# SOLENOID-SSR.net
KiCad netlist of a schematic drawn in Altium Designer
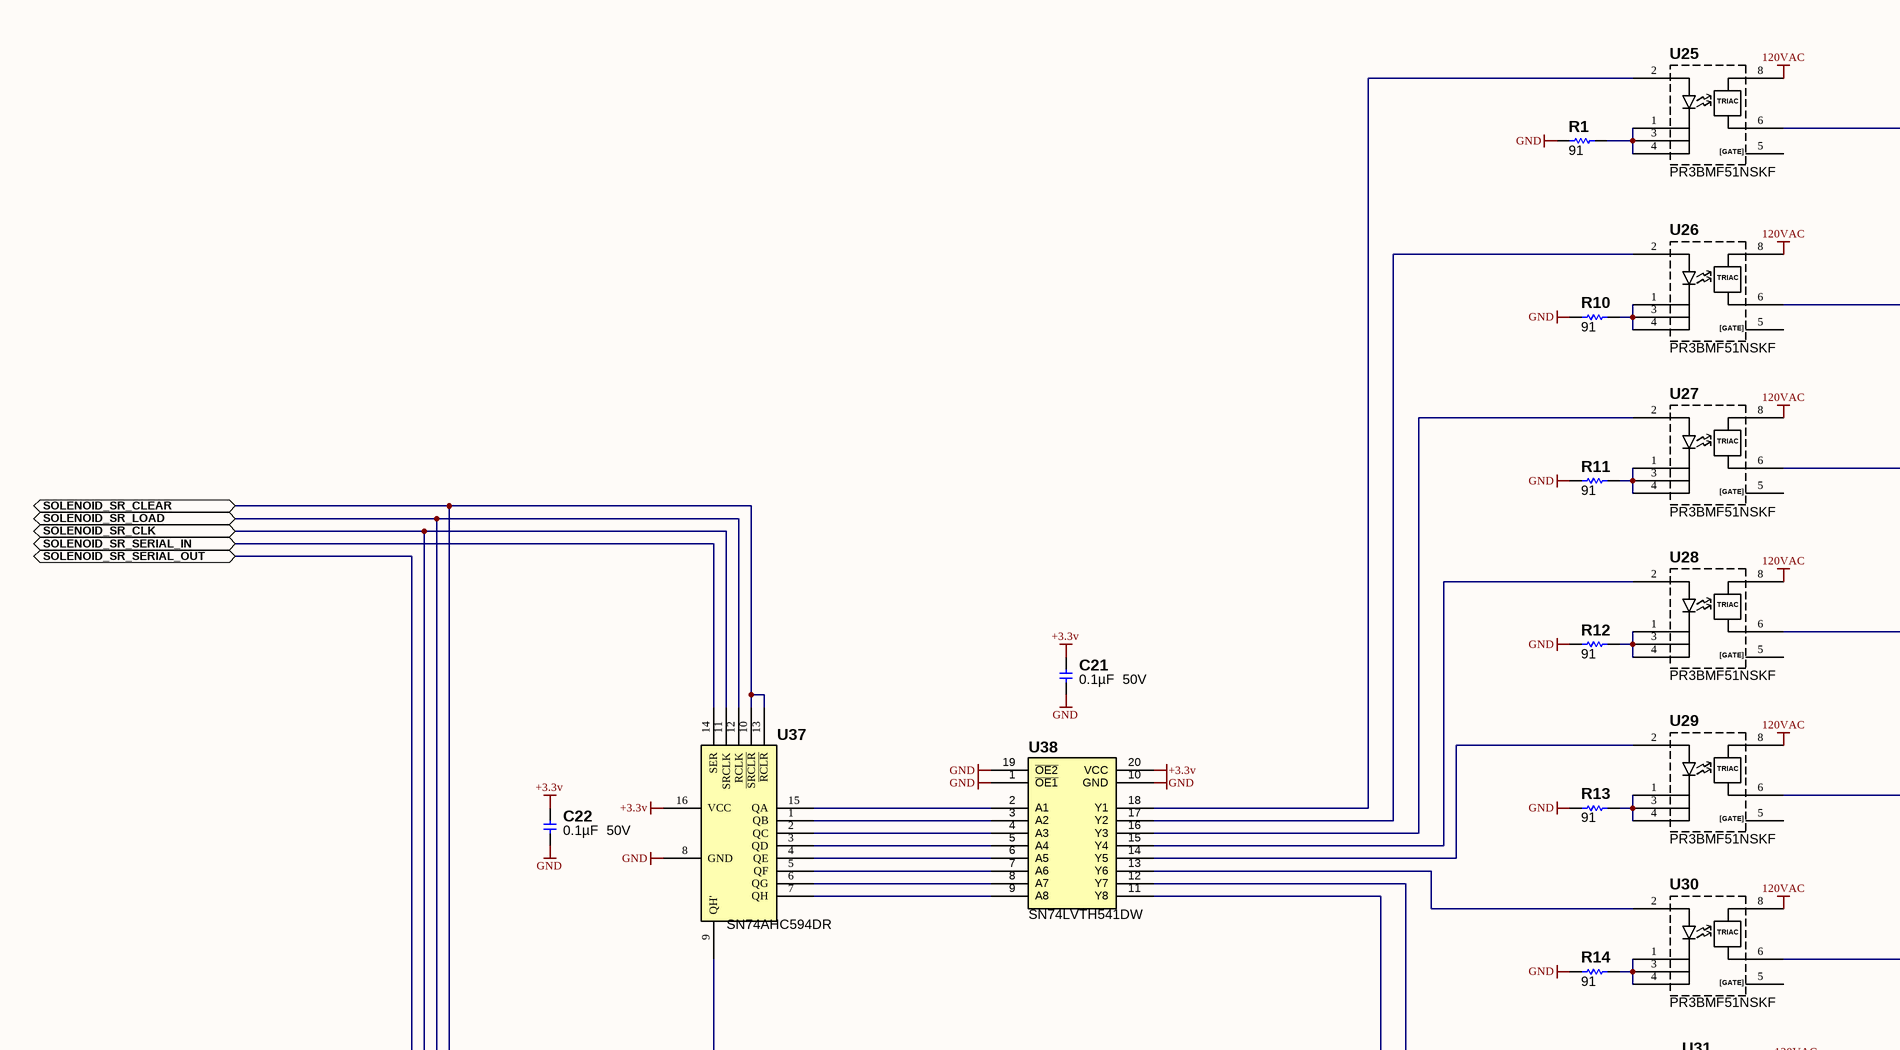
[diagram p0: SOLENOID-SSR.SchDoc, top left]
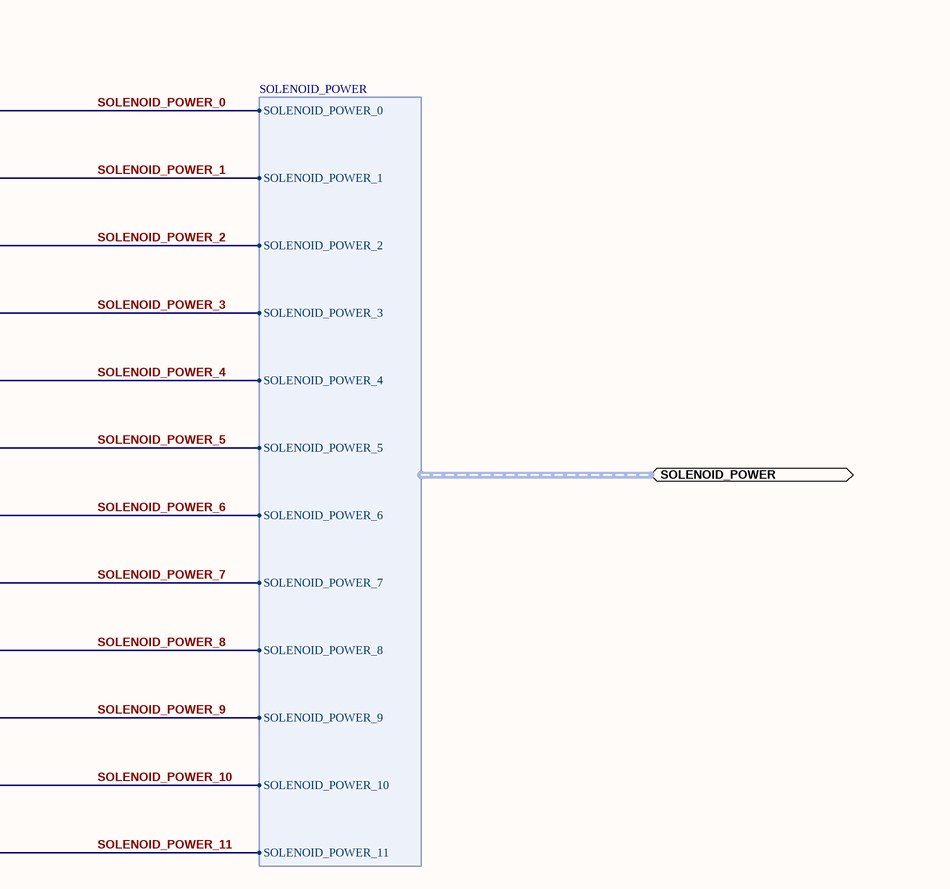
[diagram p1: SOLENOID-SSR.SchDoc, top right]
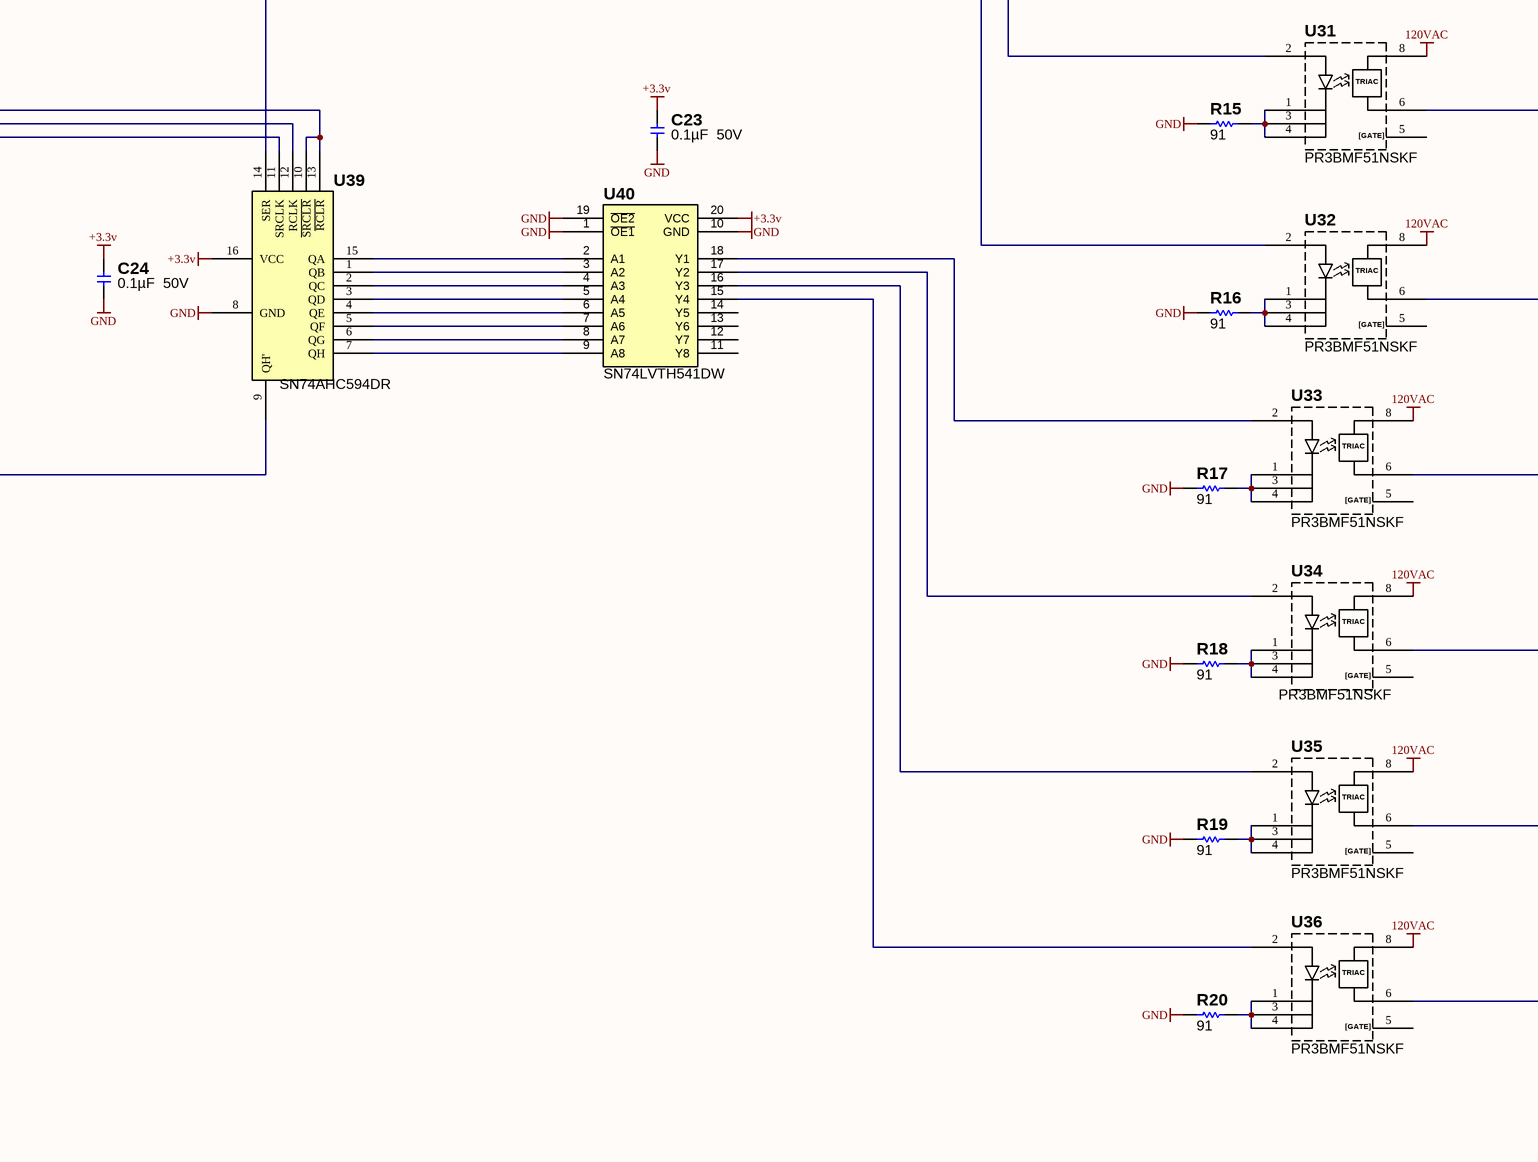
[diagram p2: SOLENOID-SSR.SchDoc, bottom left]
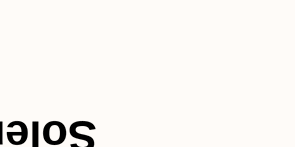
[diagram p3: SOLENOID-SSR.SchDoc, bottom right]

(export (version "E")
  (design (tool "Eeschema 10.0.6"))
  (components
    (comp (ref "C21")
      (value "0.1µF  50V")
      (footprint "C0805_LD")
      (description "CAP CER 0.1UF 50V 10% X7R 0805")
      (fields
        (field (name "MANUFACTURER PART NUMBER") "GRM21BR71H104KA01L")
        (field (name "MANUFACTURER") "Murata Electronics North America")
      )
      (libsource (lib "Capacitors") (part "C_2P_NP"))
    )
    (comp (ref "C22")
      (value "0.1µF  50V")
      (footprint "C0805_LD")
      (description "CAP CER 0.1UF 50V 10% X7R 0805")
      (fields
        (field (name "MANUFACTURER PART NUMBER") "GRM21BR71H104KA01L")
        (field (name "MANUFACTURER") "Murata Electronics North America")
      )
      (libsource (lib "Capacitors") (part "C_2P_NP"))
    )
    (comp (ref "C23")
      (value "0.1µF  50V")
      (footprint "C0805_LD")
      (description "CAP CER 0.1UF 50V 10% X7R 0805")
      (fields
        (field (name "MANUFACTURER PART NUMBER") "GRM21BR71H104KA01L")
        (field (name "MANUFACTURER") "Murata Electronics North America")
      )
      (libsource (lib "Capacitors") (part "C_2P_NP"))
    )
    (comp (ref "C24")
      (value "0.1µF  50V")
      (footprint "C0805_LD")
      (description "CAP CER 0.1UF 50V 10% X7R 0805")
      (fields
        (field (name "MANUFACTURER PART NUMBER") "GRM21BR71H104KA01L")
        (field (name "MANUFACTURER") "Murata Electronics North America")
      )
      (libsource (lib "Capacitors") (part "C_2P_NP"))
    )
    (comp (ref "R1")
      (value "91")
      (footprint "R0805_LD")
      (description "RES 91 OHM 1/8W 1% 0805 SMD")
      (fields
        (field (name "MANUFACTURER PART NUMBER") "ERJ-6ENF91R0V")
        (field (name "MANUFACTURER") "Panasonic Electronic Components")
      )
      (libsource (lib "Resistors") (part "R_2P"))
    )
    (comp (ref "R10")
      (value "91")
      (footprint "R0805_LD")
      (description "RES 91 OHM 1/8W 1% 0805 SMD")
      (fields
        (field (name "MANUFACTURER PART NUMBER") "ERJ-6ENF91R0V")
        (field (name "MANUFACTURER") "Panasonic Electronic Components")
      )
      (libsource (lib "Resistors") (part "R_2P"))
    )
    (comp (ref "R11")
      (value "91")
      (footprint "R0805_LD")
      (description "RES 91 OHM 1/8W 1% 0805 SMD")
      (fields
        (field (name "MANUFACTURER PART NUMBER") "ERJ-6ENF91R0V")
        (field (name "MANUFACTURER") "Panasonic Electronic Components")
      )
      (libsource (lib "Resistors") (part "R_2P"))
    )
    (comp (ref "R12")
      (value "91")
      (footprint "R0805_LD")
      (description "RES 91 OHM 1/8W 1% 0805 SMD")
      (fields
        (field (name "MANUFACTURER PART NUMBER") "ERJ-6ENF91R0V")
        (field (name "MANUFACTURER") "Panasonic Electronic Components")
      )
      (libsource (lib "Resistors") (part "R_2P"))
    )
    (comp (ref "R13")
      (value "91")
      (footprint "R0805_LD")
      (description "RES 91 OHM 1/8W 1% 0805 SMD")
      (fields
        (field (name "MANUFACTURER PART NUMBER") "ERJ-6ENF91R0V")
        (field (name "MANUFACTURER") "Panasonic Electronic Components")
      )
      (libsource (lib "Resistors") (part "R_2P"))
    )
    (comp (ref "R14")
      (value "91")
      (footprint "R0805_LD")
      (description "RES 91 OHM 1/8W 1% 0805 SMD")
      (fields
        (field (name "MANUFACTURER PART NUMBER") "ERJ-6ENF91R0V")
        (field (name "MANUFACTURER") "Panasonic Electronic Components")
      )
      (libsource (lib "Resistors") (part "R_2P"))
    )
    (comp (ref "R15")
      (value "91")
      (footprint "R0805_LD")
      (description "RES 91 OHM 1/8W 1% 0805 SMD")
      (fields
        (field (name "MANUFACTURER PART NUMBER") "ERJ-6ENF91R0V")
        (field (name "MANUFACTURER") "Panasonic Electronic Components")
      )
      (libsource (lib "Resistors") (part "R_2P"))
    )
    (comp (ref "R16")
      (value "91")
      (footprint "R0805_LD")
      (description "RES 91 OHM 1/8W 1% 0805 SMD")
      (fields
        (field (name "MANUFACTURER PART NUMBER") "ERJ-6ENF91R0V")
        (field (name "MANUFACTURER") "Panasonic Electronic Components")
      )
      (libsource (lib "Resistors") (part "R_2P"))
    )
    (comp (ref "R17")
      (value "91")
      (footprint "R0805_LD")
      (description "RES 91 OHM 1/8W 1% 0805 SMD")
      (fields
        (field (name "MANUFACTURER PART NUMBER") "ERJ-6ENF91R0V")
        (field (name "MANUFACTURER") "Panasonic Electronic Components")
      )
      (libsource (lib "Resistors") (part "R_2P"))
    )
    (comp (ref "R18")
      (value "91")
      (footprint "R0805_LD")
      (description "RES 91 OHM 1/8W 1% 0805 SMD")
      (fields
        (field (name "MANUFACTURER PART NUMBER") "ERJ-6ENF91R0V")
        (field (name "MANUFACTURER") "Panasonic Electronic Components")
      )
      (libsource (lib "Resistors") (part "R_2P"))
    )
    (comp (ref "R19")
      (value "91")
      (footprint "R0805_LD")
      (description "RES 91 OHM 1/8W 1% 0805 SMD")
      (fields
        (field (name "MANUFACTURER PART NUMBER") "ERJ-6ENF91R0V")
        (field (name "MANUFACTURER") "Panasonic Electronic Components")
      )
      (libsource (lib "Resistors") (part "R_2P"))
    )
    (comp (ref "R20")
      (value "91")
      (footprint "R0805_LD")
      (description "RES 91 OHM 1/8W 1% 0805 SMD")
      (fields
        (field (name "MANUFACTURER PART NUMBER") "ERJ-6ENF91R0V")
        (field (name "MANUFACTURER") "Panasonic Electronic Components")
      )
      (libsource (lib "Resistors") (part "R_2P"))
    )
    (comp (ref "U25")
      (value "PR3BMF51NSKF")
      (footprint "DIP8_NO_PIN7")
      (description "RELAY SSR 10MA 240V 1.2A 8-DIP")
      (fields (field (name "MANUFACTURER") "Sharp Microelectronics"))
      (libsource (lib "eIC") (part "PR3BMF51NSKF"))
    )
    (comp (ref "U26")
      (value "PR3BMF51NSKF")
      (footprint "DIP8_NO_PIN7")
      (description "RELAY SSR 10MA 240V 1.2A 8-DIP")
      (fields (field (name "MANUFACTURER") "Sharp Microelectronics"))
      (libsource (lib "eIC") (part "PR3BMF51NSKF"))
    )
    (comp (ref "U27")
      (value "PR3BMF51NSKF")
      (footprint "DIP8_NO_PIN7")
      (description "RELAY SSR 10MA 240V 1.2A 8-DIP")
      (fields (field (name "MANUFACTURER") "Sharp Microelectronics"))
      (libsource (lib "eIC") (part "PR3BMF51NSKF"))
    )
    (comp (ref "U28")
      (value "PR3BMF51NSKF")
      (footprint "DIP8_NO_PIN7")
      (description "RELAY SSR 10MA 240V 1.2A 8-DIP")
      (fields (field (name "MANUFACTURER") "Sharp Microelectronics"))
      (libsource (lib "eIC") (part "PR3BMF51NSKF"))
    )
    (comp (ref "U29")
      (value "PR3BMF51NSKF")
      (footprint "DIP8_NO_PIN7")
      (description "RELAY SSR 10MA 240V 1.2A 8-DIP")
      (fields (field (name "MANUFACTURER") "Sharp Microelectronics"))
      (libsource (lib "eIC") (part "PR3BMF51NSKF"))
    )
    (comp (ref "U30")
      (value "PR3BMF51NSKF")
      (footprint "DIP8_NO_PIN7")
      (description "RELAY SSR 10MA 240V 1.2A 8-DIP")
      (fields (field (name "MANUFACTURER") "Sharp Microelectronics"))
      (libsource (lib "eIC") (part "PR3BMF51NSKF"))
    )
    (comp (ref "U31")
      (value "PR3BMF51NSKF")
      (footprint "DIP8_NO_PIN7")
      (description "RELAY SSR 10MA 240V 1.2A 8-DIP")
      (fields (field (name "MANUFACTURER") "Sharp Microelectronics"))
      (libsource (lib "eIC") (part "PR3BMF51NSKF"))
    )
    (comp (ref "U32")
      (value "PR3BMF51NSKF")
      (footprint "DIP8_NO_PIN7")
      (description "RELAY SSR 10MA 240V 1.2A 8-DIP")
      (fields (field (name "MANUFACTURER") "Sharp Microelectronics"))
      (libsource (lib "eIC") (part "PR3BMF51NSKF"))
    )
    (comp (ref "U33")
      (value "PR3BMF51NSKF")
      (footprint "DIP8_NO_PIN7")
      (description "RELAY SSR 10MA 240V 1.2A 8-DIP")
      (fields (field (name "MANUFACTURER") "Sharp Microelectronics"))
      (libsource (lib "eIC") (part "PR3BMF51NSKF"))
    )
    (comp (ref "U34")
      (value "PR3BMF51NSKF")
      (footprint "DIP8_NO_PIN7")
      (description "RELAY SSR 10MA 240V 1.2A 8-DIP")
      (fields (field (name "MANUFACTURER") "Sharp Microelectronics"))
      (libsource (lib "eIC") (part "PR3BMF51NSKF"))
    )
    (comp (ref "U35")
      (value "PR3BMF51NSKF")
      (footprint "DIP8_NO_PIN7")
      (description "RELAY SSR 10MA 240V 1.2A 8-DIP")
      (fields (field (name "MANUFACTURER") "Sharp Microelectronics"))
      (libsource (lib "eIC") (part "PR3BMF51NSKF"))
    )
    (comp (ref "U36")
      (value "PR3BMF51NSKF")
      (footprint "DIP8_NO_PIN7")
      (description "RELAY SSR 10MA 240V 1.2A 8-DIP")
      (fields (field (name "MANUFACTURER") "Sharp Microelectronics"))
      (libsource (lib "eIC") (part "PR3BMF51NSKF"))
    )
    (comp (ref "U37")
      (value "SN74AHC594DR")
      (footprint "SOIC127P600X145-16L")
      (description "IC SHIFT REGISTER 8BIT 16-SOIC")
      (fields (field (name "MANUFACTURER") "Texas Instruments"))
      (libsource (lib "eIC") (part "SN74AHC594DR"))
    )
    (comp (ref "U38")
      (value "SN74LVTH541DW")
      (footprint "SOIC127P1030X265-20L")
      (description "IC BUFF/DVR TRI-ST 8BIT 20SOIC")
      (fields (field (name "MANUFACTURER") "Texas Instruments"))
      (libsource (lib "eIC") (part "SN74LVTH541DW"))
    )
    (comp (ref "U39")
      (value "SN74AHC594DR")
      (footprint "SOIC127P600X145-16L")
      (description "IC SHIFT REGISTER 8BIT 16-SOIC")
      (fields (field (name "MANUFACTURER") "Texas Instruments"))
      (libsource (lib "eIC") (part "SN74AHC594DR"))
    )
    (comp (ref "U40")
      (value "SN74LVTH541DW")
      (footprint "SOIC127P1030X265-20L")
      (description "IC BUFF/DVR TRI-ST 8BIT 20SOIC")
      (fields (field (name "MANUFACTURER") "Texas Instruments"))
      (libsource (lib "eIC") (part "SN74LVTH541DW"))
    )
  )
  (nets
    (net (code "2") (name "+3.3v") (class "Default")
      (node (ref "C21") (pin "2") (pinfunction "2_2") (pintype "passive"))
      (node (ref "C22") (pin "2") (pinfunction "2_2") (pintype "passive"))
      (node (ref "C23") (pin "2") (pinfunction "2_2") (pintype "passive"))
      (node (ref "C24") (pin "2") (pinfunction "2_2") (pintype "passive"))
      (node (ref "U37") (pin "16") (pinfunction "VCC_16") (pintype "passive"))
      (node (ref "U38") (pin "20") (pinfunction "VCC_20") (pintype "passive"))
      (node (ref "U39") (pin "16") (pinfunction "VCC_16") (pintype "passive"))
      (node (ref "U40") (pin "20") (pinfunction "VCC_20") (pintype "passive"))
    )
    (net (code "3") (name "/SOLENOID_POWER_0") (class "Default")
      (node (ref "U25") (pin "6") (pinfunction "6_6") (pintype "passive"))
    )
    (net (code "4") (name "/SOLENOID_POWER_1") (class "Default")
      (node (ref "U26") (pin "6") (pinfunction "6_6") (pintype "passive"))
    )
    (net (code "5") (name "/SOLENOID_POWER_2") (class "Default")
      (node (ref "U27") (pin "6") (pinfunction "6_6") (pintype "passive"))
    )
    (net (code "6") (name "/SOLENOID_POWER_3") (class "Default")
      (node (ref "U28") (pin "6") (pinfunction "6_6") (pintype "passive"))
    )
    (net (code "7") (name "/SOLENOID_POWER_4") (class "Default")
      (node (ref "U29") (pin "6") (pinfunction "6_6") (pintype "passive"))
    )
    (net (code "8") (name "/SOLENOID_POWER_5") (class "Default")
      (node (ref "U30") (pin "6") (pinfunction "6_6") (pintype "passive"))
    )
    (net (code "9") (name "/SOLENOID_POWER_6") (class "Default")
      (node (ref "U31") (pin "6") (pinfunction "6_6") (pintype "passive"))
    )
    (net (code "10") (name "/SOLENOID_POWER_7") (class "Default")
      (node (ref "U32") (pin "6") (pinfunction "6_6") (pintype "passive"))
    )
    (net (code "11") (name "/SOLENOID_POWER_8") (class "Default")
      (node (ref "U33") (pin "6") (pinfunction "6_6") (pintype "passive"))
    )
    (net (code "12") (name "/SOLENOID_POWER_9") (class "Default")
      (node (ref "U34") (pin "6") (pinfunction "6_6") (pintype "passive"))
    )
    (net (code "13") (name "/SOLENOID_POWER_10") (class "Default")
      (node (ref "U35") (pin "6") (pinfunction "6_6") (pintype "passive"))
    )
    (net (code "14") (name "/SOLENOID_POWER_11") (class "Default")
      (node (ref "U36") (pin "6") (pinfunction "6_6") (pintype "passive"))
    )
    (net (code "15") (name "/SOLENOID_SR_CLEAR") (class "Default")
      (node (ref "U37") (pin "10") (pinfunction "~{SRCLR}_10") (pintype "passive"))
      (node (ref "U37") (pin "13") (pinfunction "~{RCLR}_13") (pintype "passive"))
      (node (ref "U39") (pin "10") (pinfunction "~{SRCLR}_10") (pintype "passive"))
      (node (ref "U39") (pin "13") (pinfunction "~{RCLR}_13") (pintype "passive"))
    )
    (net (code "16") (name "/SOLENOID_SR_CLK") (class "Default")
      (node (ref "U37") (pin "11") (pinfunction "SRCLK_11") (pintype "passive"))
      (node (ref "U39") (pin "11") (pinfunction "SRCLK_11") (pintype "passive"))
    )
    (net (code "17") (name "/SOLENOID_SR_LOAD") (class "Default")
      (node (ref "U37") (pin "12") (pinfunction "RCLK_12") (pintype "passive"))
      (node (ref "U39") (pin "12") (pinfunction "RCLK_12") (pintype "passive"))
    )
    (net (code "18") (name "/SOLENOID_SR_SERIAL_IN") (class "Default")
      (node (ref "U37") (pin "14") (pinfunction "SER_14") (pintype "passive"))
    )
    (net (code "19") (name "/SOLENOID_SR_SERIAL_OUT") (class "Default")
      (node (ref "U39") (pin "9") (pinfunction "QH'_9") (pintype "passive"))
    )
    (net (code "21") (name "120VAC") (class "Default")
      (node (ref "U25") (pin "8") (pinfunction "8_8") (pintype "passive"))
      (node (ref "U26") (pin "8") (pinfunction "8_8") (pintype "passive"))
      (node (ref "U27") (pin "8") (pinfunction "8_8") (pintype "passive"))
      (node (ref "U28") (pin "8") (pinfunction "8_8") (pintype "passive"))
      (node (ref "U29") (pin "8") (pinfunction "8_8") (pintype "passive"))
      (node (ref "U30") (pin "8") (pinfunction "8_8") (pintype "passive"))
      (node (ref "U31") (pin "8") (pinfunction "8_8") (pintype "passive"))
      (node (ref "U32") (pin "8") (pinfunction "8_8") (pintype "passive"))
      (node (ref "U33") (pin "8") (pinfunction "8_8") (pintype "passive"))
      (node (ref "U34") (pin "8") (pinfunction "8_8") (pintype "passive"))
      (node (ref "U35") (pin "8") (pinfunction "8_8") (pintype "passive"))
      (node (ref "U36") (pin "8") (pinfunction "8_8") (pintype "passive"))
    )
    (net (code "22") (name "GND") (class "Default")
      (node (ref "C21") (pin "1") (pinfunction "1_1") (pintype "passive"))
      (node (ref "C22") (pin "1") (pinfunction "1_1") (pintype "passive"))
      (node (ref "C23") (pin "1") (pinfunction "1_1") (pintype "passive"))
      (node (ref "C24") (pin "1") (pinfunction "1_1") (pintype "passive"))
      (node (ref "R1") (pin "1") (pinfunction "1_1") (pintype "passive"))
      (node (ref "R10") (pin "1") (pinfunction "1_1") (pintype "passive"))
      (node (ref "R11") (pin "1") (pinfunction "1_1") (pintype "passive"))
      (node (ref "R12") (pin "1") (pinfunction "1_1") (pintype "passive"))
      (node (ref "R13") (pin "1") (pinfunction "1_1") (pintype "passive"))
      (node (ref "R14") (pin "1") (pinfunction "1_1") (pintype "passive"))
      (node (ref "R15") (pin "1") (pinfunction "1_1") (pintype "passive"))
      (node (ref "R16") (pin "1") (pinfunction "1_1") (pintype "passive"))
      (node (ref "R17") (pin "1") (pinfunction "1_1") (pintype "passive"))
      (node (ref "R18") (pin "1") (pinfunction "1_1") (pintype "passive"))
      (node (ref "R19") (pin "1") (pinfunction "1_1") (pintype "passive"))
      (node (ref "R20") (pin "1") (pinfunction "1_1") (pintype "passive"))
      (node (ref "U37") (pin "8") (pinfunction "GND_8") (pintype "passive"))
      (node (ref "U38") (pin "1") (pinfunction "~{OE1}_1") (pintype "passive"))
      (node (ref "U38") (pin "10") (pinfunction "GND_10") (pintype "passive"))
      (node (ref "U38") (pin "19") (pinfunction "~{OE2}_19") (pintype "passive"))
      (node (ref "U39") (pin "8") (pinfunction "GND_8") (pintype "passive"))
      (node (ref "U40") (pin "1") (pinfunction "~{OE1}_1") (pintype "passive"))
      (node (ref "U40") (pin "10") (pinfunction "GND_10") (pintype "passive"))
      (node (ref "U40") (pin "19") (pinfunction "~{OE2}_19") (pintype "passive"))
    )
    (net (code "23") (name "Net-(R1-Pad2)") (class "Default")
      (node (ref "R1") (pin "2") (pinfunction "2_2") (pintype "passive"))
      (node (ref "U25") (pin "1") (pinfunction "1_1") (pintype "passive"))
      (node (ref "U25") (pin "3") (pinfunction "3_3") (pintype "passive"))
      (node (ref "U25") (pin "4") (pinfunction "4_4") (pintype "passive"))
    )
    (net (code "24") (name "Net-(R10-Pad2)") (class "Default")
      (node (ref "R10") (pin "2") (pinfunction "2_2") (pintype "passive"))
      (node (ref "U26") (pin "1") (pinfunction "1_1") (pintype "passive"))
      (node (ref "U26") (pin "3") (pinfunction "3_3") (pintype "passive"))
      (node (ref "U26") (pin "4") (pinfunction "4_4") (pintype "passive"))
    )
    (net (code "25") (name "Net-(R11-Pad2)") (class "Default")
      (node (ref "R11") (pin "2") (pinfunction "2_2") (pintype "passive"))
      (node (ref "U27") (pin "1") (pinfunction "1_1") (pintype "passive"))
      (node (ref "U27") (pin "3") (pinfunction "3_3") (pintype "passive"))
      (node (ref "U27") (pin "4") (pinfunction "4_4") (pintype "passive"))
    )
    (net (code "26") (name "Net-(R12-Pad2)") (class "Default")
      (node (ref "R12") (pin "2") (pinfunction "2_2") (pintype "passive"))
      (node (ref "U28") (pin "1") (pinfunction "1_1") (pintype "passive"))
      (node (ref "U28") (pin "3") (pinfunction "3_3") (pintype "passive"))
      (node (ref "U28") (pin "4") (pinfunction "4_4") (pintype "passive"))
    )
    (net (code "27") (name "Net-(R13-Pad2)") (class "Default")
      (node (ref "R13") (pin "2") (pinfunction "2_2") (pintype "passive"))
      (node (ref "U29") (pin "1") (pinfunction "1_1") (pintype "passive"))
      (node (ref "U29") (pin "3") (pinfunction "3_3") (pintype "passive"))
      (node (ref "U29") (pin "4") (pinfunction "4_4") (pintype "passive"))
    )
    (net (code "28") (name "Net-(R14-Pad2)") (class "Default")
      (node (ref "R14") (pin "2") (pinfunction "2_2") (pintype "passive"))
      (node (ref "U30") (pin "1") (pinfunction "1_1") (pintype "passive"))
      (node (ref "U30") (pin "3") (pinfunction "3_3") (pintype "passive"))
      (node (ref "U30") (pin "4") (pinfunction "4_4") (pintype "passive"))
    )
    (net (code "29") (name "Net-(R15-Pad2)") (class "Default")
      (node (ref "R15") (pin "2") (pinfunction "2_2") (pintype "passive"))
      (node (ref "U31") (pin "1") (pinfunction "1_1") (pintype "passive"))
      (node (ref "U31") (pin "3") (pinfunction "3_3") (pintype "passive"))
      (node (ref "U31") (pin "4") (pinfunction "4_4") (pintype "passive"))
    )
    (net (code "30") (name "Net-(R16-Pad2)") (class "Default")
      (node (ref "R16") (pin "2") (pinfunction "2_2") (pintype "passive"))
      (node (ref "U32") (pin "1") (pinfunction "1_1") (pintype "passive"))
      (node (ref "U32") (pin "3") (pinfunction "3_3") (pintype "passive"))
      (node (ref "U32") (pin "4") (pinfunction "4_4") (pintype "passive"))
    )
    (net (code "31") (name "Net-(R17-Pad2)") (class "Default")
      (node (ref "R17") (pin "2") (pinfunction "2_2") (pintype "passive"))
      (node (ref "U33") (pin "1") (pinfunction "1_1") (pintype "passive"))
      (node (ref "U33") (pin "3") (pinfunction "3_3") (pintype "passive"))
      (node (ref "U33") (pin "4") (pinfunction "4_4") (pintype "passive"))
    )
    (net (code "32") (name "Net-(R18-Pad2)") (class "Default")
      (node (ref "R18") (pin "2") (pinfunction "2_2") (pintype "passive"))
      (node (ref "U34") (pin "1") (pinfunction "1_1") (pintype "passive"))
      (node (ref "U34") (pin "3") (pinfunction "3_3") (pintype "passive"))
      (node (ref "U34") (pin "4") (pinfunction "4_4") (pintype "passive"))
    )
    (net (code "33") (name "Net-(R19-Pad2)") (class "Default")
      (node (ref "R19") (pin "2") (pinfunction "2_2") (pintype "passive"))
      (node (ref "U35") (pin "1") (pinfunction "1_1") (pintype "passive"))
      (node (ref "U35") (pin "3") (pinfunction "3_3") (pintype "passive"))
      (node (ref "U35") (pin "4") (pinfunction "4_4") (pintype "passive"))
    )
    (net (code "34") (name "Net-(R20-Pad2)") (class "Default")
      (node (ref "R20") (pin "2") (pinfunction "2_2") (pintype "passive"))
      (node (ref "U36") (pin "1") (pinfunction "1_1") (pintype "passive"))
      (node (ref "U36") (pin "3") (pinfunction "3_3") (pintype "passive"))
      (node (ref "U36") (pin "4") (pinfunction "4_4") (pintype "passive"))
    )
    (net (code "35") (name "Net-(U37-QA)") (class "Default")
      (node (ref "U37") (pin "15") (pinfunction "QA_15") (pintype "passive"))
      (node (ref "U38") (pin "2") (pinfunction "A1_2") (pintype "passive"))
    )
    (net (code "36") (name "Net-(U37-QB)") (class "Default")
      (node (ref "U37") (pin "1") (pinfunction "QB_1") (pintype "passive"))
      (node (ref "U38") (pin "3") (pinfunction "A2_3") (pintype "passive"))
    )
    (net (code "37") (name "Net-(U37-QC)") (class "Default")
      (node (ref "U37") (pin "2") (pinfunction "QC_2") (pintype "passive"))
      (node (ref "U38") (pin "4") (pinfunction "A3_4") (pintype "passive"))
    )
    (net (code "38") (name "Net-(U37-QD)") (class "Default")
      (node (ref "U37") (pin "3") (pinfunction "QD_3") (pintype "passive"))
      (node (ref "U38") (pin "5") (pinfunction "A4_5") (pintype "passive"))
    )
    (net (code "39") (name "Net-(U37-QE)") (class "Default")
      (node (ref "U37") (pin "4") (pinfunction "QE_4") (pintype "passive"))
      (node (ref "U38") (pin "6") (pinfunction "A5_6") (pintype "passive"))
    )
    (net (code "40") (name "Net-(U37-QF)") (class "Default")
      (node (ref "U37") (pin "5") (pinfunction "QF_5") (pintype "passive"))
      (node (ref "U38") (pin "7") (pinfunction "A6_7") (pintype "passive"))
    )
    (net (code "41") (name "Net-(U37-QG)") (class "Default")
      (node (ref "U37") (pin "6") (pinfunction "QG_6") (pintype "passive"))
      (node (ref "U38") (pin "8") (pinfunction "A7_8") (pintype "passive"))
    )
    (net (code "42") (name "Net-(U37-QH')") (class "Default")
      (node (ref "U37") (pin "9") (pinfunction "QH'_9") (pintype "passive"))
      (node (ref "U39") (pin "14") (pinfunction "SER_14") (pintype "passive"))
    )
    (net (code "43") (name "Net-(U37-QH)") (class "Default")
      (node (ref "U37") (pin "7") (pinfunction "QH_7") (pintype "passive"))
      (node (ref "U38") (pin "9") (pinfunction "A8_9") (pintype "passive"))
    )
    (net (code "44") (name "Net-(U38-Y1)") (class "Default")
      (node (ref "U25") (pin "2") (pinfunction "2_2") (pintype "passive"))
      (node (ref "U38") (pin "18") (pinfunction "Y1_18") (pintype "passive"))
    )
    (net (code "45") (name "Net-(U38-Y2)") (class "Default")
      (node (ref "U26") (pin "2") (pinfunction "2_2") (pintype "passive"))
      (node (ref "U38") (pin "17") (pinfunction "Y2_17") (pintype "passive"))
    )
    (net (code "46") (name "Net-(U38-Y3)") (class "Default")
      (node (ref "U27") (pin "2") (pinfunction "2_2") (pintype "passive"))
      (node (ref "U38") (pin "16") (pinfunction "Y3_16") (pintype "passive"))
    )
    (net (code "47") (name "Net-(U38-Y4)") (class "Default")
      (node (ref "U28") (pin "2") (pinfunction "2_2") (pintype "passive"))
      (node (ref "U38") (pin "15") (pinfunction "Y4_15") (pintype "passive"))
    )
    (net (code "48") (name "Net-(U38-Y5)") (class "Default")
      (node (ref "U29") (pin "2") (pinfunction "2_2") (pintype "passive"))
      (node (ref "U38") (pin "14") (pinfunction "Y5_14") (pintype "passive"))
    )
    (net (code "49") (name "Net-(U38-Y6)") (class "Default")
      (node (ref "U30") (pin "2") (pinfunction "2_2") (pintype "passive"))
      (node (ref "U38") (pin "13") (pinfunction "Y6_13") (pintype "passive"))
    )
    (net (code "50") (name "Net-(U38-Y7)") (class "Default")
      (node (ref "U31") (pin "2") (pinfunction "2_2") (pintype "passive"))
      (node (ref "U38") (pin "12") (pinfunction "Y7_12") (pintype "passive"))
    )
    (net (code "51") (name "Net-(U38-Y8)") (class "Default")
      (node (ref "U32") (pin "2") (pinfunction "2_2") (pintype "passive"))
      (node (ref "U38") (pin "11") (pinfunction "Y8_11") (pintype "passive"))
    )
    (net (code "52") (name "Net-(U39-QA)") (class "Default")
      (node (ref "U39") (pin "15") (pinfunction "QA_15") (pintype "passive"))
      (node (ref "U40") (pin "2") (pinfunction "A1_2") (pintype "passive"))
    )
    (net (code "53") (name "Net-(U39-QB)") (class "Default")
      (node (ref "U39") (pin "1") (pinfunction "QB_1") (pintype "passive"))
      (node (ref "U40") (pin "3") (pinfunction "A2_3") (pintype "passive"))
    )
    (net (code "54") (name "Net-(U39-QC)") (class "Default")
      (node (ref "U39") (pin "2") (pinfunction "QC_2") (pintype "passive"))
      (node (ref "U40") (pin "4") (pinfunction "A3_4") (pintype "passive"))
    )
    (net (code "55") (name "Net-(U39-QD)") (class "Default")
      (node (ref "U39") (pin "3") (pinfunction "QD_3") (pintype "passive"))
      (node (ref "U40") (pin "5") (pinfunction "A4_5") (pintype "passive"))
    )
    (net (code "56") (name "Net-(U39-QE)") (class "Default")
      (node (ref "U39") (pin "4") (pinfunction "QE_4") (pintype "passive"))
      (node (ref "U40") (pin "6") (pinfunction "A5_6") (pintype "passive"))
    )
    (net (code "57") (name "Net-(U39-QF)") (class "Default")
      (node (ref "U39") (pin "5") (pinfunction "QF_5") (pintype "passive"))
      (node (ref "U40") (pin "7") (pinfunction "A6_7") (pintype "passive"))
    )
    (net (code "58") (name "Net-(U39-QG)") (class "Default")
      (node (ref "U39") (pin "6") (pinfunction "QG_6") (pintype "passive"))
      (node (ref "U40") (pin "8") (pinfunction "A7_8") (pintype "passive"))
    )
    (net (code "59") (name "Net-(U39-QH)") (class "Default")
      (node (ref "U39") (pin "7") (pinfunction "QH_7") (pintype "passive"))
      (node (ref "U40") (pin "9") (pinfunction "A8_9") (pintype "passive"))
    )
    (net (code "60") (name "Net-(U40-Y1)") (class "Default")
      (node (ref "U33") (pin "2") (pinfunction "2_2") (pintype "passive"))
      (node (ref "U40") (pin "18") (pinfunction "Y1_18") (pintype "passive"))
    )
    (net (code "61") (name "Net-(U40-Y2)") (class "Default")
      (node (ref "U34") (pin "2") (pinfunction "2_2") (pintype "passive"))
      (node (ref "U40") (pin "17") (pinfunction "Y2_17") (pintype "passive"))
    )
    (net (code "62") (name "Net-(U40-Y3)") (class "Default")
      (node (ref "U35") (pin "2") (pinfunction "2_2") (pintype "passive"))
      (node (ref "U40") (pin "16") (pinfunction "Y3_16") (pintype "passive"))
    )
    (net (code "63") (name "Net-(U40-Y4)") (class "Default")
      (node (ref "U36") (pin "2") (pinfunction "2_2") (pintype "passive"))
      (node (ref "U40") (pin "15") (pinfunction "Y4_15") (pintype "passive"))
    )
    (net (code "64") (name "unconnected-(U25-Pad5)") (class "Default")
      (node (ref "U25") (pin "5") (pinfunction "5_5") (pintype "passive"))
    )
    (net (code "65") (name "unconnected-(U26-Pad5)") (class "Default")
      (node (ref "U26") (pin "5") (pinfunction "5_5") (pintype "passive"))
    )
    (net (code "66") (name "unconnected-(U27-Pad5)") (class "Default")
      (node (ref "U27") (pin "5") (pinfunction "5_5") (pintype "passive"))
    )
    (net (code "67") (name "unconnected-(U28-Pad5)") (class "Default")
      (node (ref "U28") (pin "5") (pinfunction "5_5") (pintype "passive"))
    )
    (net (code "68") (name "unconnected-(U29-Pad5)") (class "Default")
      (node (ref "U29") (pin "5") (pinfunction "5_5") (pintype "passive"))
    )
    (net (code "69") (name "unconnected-(U30-Pad5)") (class "Default")
      (node (ref "U30") (pin "5") (pinfunction "5_5") (pintype "passive"))
    )
    (net (code "70") (name "unconnected-(U31-Pad5)") (class "Default")
      (node (ref "U31") (pin "5") (pinfunction "5_5") (pintype "passive"))
    )
    (net (code "71") (name "unconnected-(U32-Pad5)") (class "Default")
      (node (ref "U32") (pin "5") (pinfunction "5_5") (pintype "passive"))
    )
    (net (code "72") (name "unconnected-(U33-Pad5)") (class "Default")
      (node (ref "U33") (pin "5") (pinfunction "5_5") (pintype "passive"))
    )
    (net (code "73") (name "unconnected-(U34-Pad5)") (class "Default")
      (node (ref "U34") (pin "5") (pinfunction "5_5") (pintype "passive"))
    )
    (net (code "74") (name "unconnected-(U35-Pad5)") (class "Default")
      (node (ref "U35") (pin "5") (pinfunction "5_5") (pintype "passive"))
    )
    (net (code "75") (name "unconnected-(U36-Pad5)") (class "Default")
      (node (ref "U36") (pin "5") (pinfunction "5_5") (pintype "passive"))
    )
    (net (code "76") (name "unconnected-(U40-Y5-Pad14)") (class "Default")
      (node (ref "U40") (pin "14") (pinfunction "Y5_14") (pintype "passive"))
    )
    (net (code "77") (name "unconnected-(U40-Y6-Pad13)") (class "Default")
      (node (ref "U40") (pin "13") (pinfunction "Y6_13") (pintype "passive"))
    )
    (net (code "78") (name "unconnected-(U40-Y7-Pad12)") (class "Default")
      (node (ref "U40") (pin "12") (pinfunction "Y7_12") (pintype "passive"))
    )
    (net (code "79") (name "unconnected-(U40-Y8-Pad11)") (class "Default")
      (node (ref "U40") (pin "11") (pinfunction "Y8_11") (pintype "passive"))
    )
  )
)
